# LED.net
KiCad netlist of a schematic drawn in Altium Designer
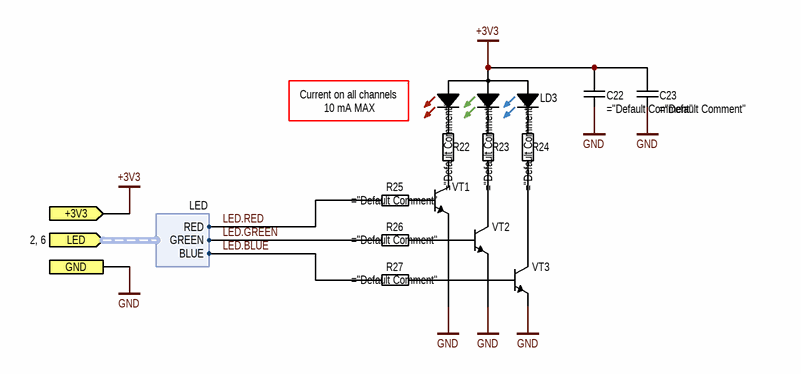
[diagram p0: LED.SchDoc]

(export (version "E")
  (design (tool "Eeschema 10.0.6"))
  (components
    (comp (ref "C22")
      (value "~")
      (description "CAP CER 10UF 10V X5R 0805")
      (fields (field (name "TOLERANCE") "10 %") (field (name "MANUFACTURER") "YAGEO"))
      (libsource (lib "femtoino") (part "CC0805KPX5R6BB106"))
    )
    (comp (ref "C23")
      (value "~")
      (description "CAP CER 1UF 10V X5R 0805")
      (fields (field (name "TOLERANCE") "10 %") (field (name "MANUFACTURER") "YAGEO"))
      (libsource (lib "femtoino") (part "CC0805KKX5R6BB105"))
    )
    (comp (ref "LD3")
      (value "~")
      (description "LED RGB DIFFUSED SMD")
      (fields (field (name "TOLERANCE") "* %") (field (name "MANUFACTURER") "Würth Elektronik"))
      (libsource (lib "femtoino") (part "150066M153000"))
    )
    (comp (ref "R22")
      (value "~")
      (description "RES 10 OHM 1% 1/10W 0603")
      (fields (field (name "TOLERANCE") "1 %") (field (name "MANUFACTURER") "YAGEO"))
      (libsource (lib "femtoino") (part "RC0603FR-0710RL"))
    )
    (comp (ref "R23")
      (value "~")
      (description "RES 10 OHM 1% 1/10W 0603")
      (fields (field (name "TOLERANCE") "1 %") (field (name "MANUFACTURER") "YAGEO"))
      (libsource (lib "femtoino") (part "RC0603FR-0710RL"))
    )
    (comp (ref "R24")
      (value "~")
      (description "RES 133 OHM 1% 1/10W 0603")
      (fields (field (name "TOLERANCE") "1 %") (field (name "MANUFACTURER") "YAGEO"))
      (libsource (lib "femtoino") (part "RC0603FR-07133RL"))
    )
    (comp (ref "R25")
      (value "~")
      (description "RES 1K OHM 1% 1/10W 0603")
      (fields (field (name "TOLERANCE") "1 %") (field (name "MANUFACTURER") "YAGEO"))
      (libsource (lib "femtoino") (part "RC0603FR-071KL"))
    )
    (comp (ref "R26")
      (value "~")
      (description "RES 1K OHM 1% 1/10W 0603")
      (fields (field (name "TOLERANCE") "1 %") (field (name "MANUFACTURER") "YAGEO"))
      (libsource (lib "femtoino") (part "RC0603FR-071KL"))
    )
    (comp (ref "R27")
      (value "~")
      (description "RES 1K OHM 1% 1/10W 0603")
      (fields (field (name "TOLERANCE") "1 %") (field (name "MANUFACTURER") "YAGEO"))
      (libsource (lib "femtoino") (part "RC0603FR-071KL"))
    )
    (comp (ref "VT1")
      (value "~")
      (description "TRANS NPN 40V 0.6A SOT23")
      (fields (field (name "TOLERANCE") "* %") (field (name "MANUFACTURER") "Micro Commercial Co"))
      (libsource (lib "femtoino") (part "MMBT2222A-TP"))
    )
    (comp (ref "VT2")
      (value "~")
      (description "TRANS NPN 40V 0.6A SOT23")
      (fields (field (name "TOLERANCE") "* %") (field (name "MANUFACTURER") "Micro Commercial Co"))
      (libsource (lib "femtoino") (part "MMBT2222A-TP"))
    )
    (comp (ref "VT3")
      (value "~")
      (description "TRANS NPN 40V 0.6A SOT23")
      (fields (field (name "TOLERANCE") "* %") (field (name "MANUFACTURER") "Micro Commercial Co"))
      (libsource (lib "femtoino") (part "MMBT2222A-TP"))
    )
  )
  (nets
    (net (code "2") (name "+3V3") (class "Default")
      (node (ref "C22") (pin "2") (pinfunction "2_2") (pintype "passive"))
      (node (ref "C23") (pin "2") (pinfunction "2_2") (pintype "passive"))
      (node (ref "LD3") (pin "CA") (pinfunction "CA_CA") (pintype "passive"))
    )
    (net (code "3") (name "/LED.BLUE") (class "Default")
      (node (ref "R27") (pin "1") (pinfunction "1_1") (pintype "passive"))
    )
    (net (code "4") (name "/LED.GREEN") (class "Default")
      (node (ref "R26") (pin "1") (pinfunction "1_1") (pintype "passive"))
    )
    (net (code "5") (name "/LED.RED") (class "Default")
      (node (ref "R25") (pin "1") (pinfunction "1_1") (pintype "passive"))
    )
    (net (code "7") (name "GND") (class "Default")
      (node (ref "C22") (pin "1") (pinfunction "1_1") (pintype "passive"))
      (node (ref "C23") (pin "1") (pinfunction "1_1") (pintype "passive"))
      (node (ref "VT1") (pin "E") (pinfunction "E_E") (pintype "passive"))
      (node (ref "VT2") (pin "E") (pinfunction "E_E") (pintype "passive"))
      (node (ref "VT3") (pin "E") (pinfunction "E_E") (pintype "passive"))
    )
    (net (code "8") (name "Net-(LD3-PadBC)") (class "Default")
      (node (ref "LD3") (pin "BC") (pinfunction "BC_BC") (pintype "passive"))
      (node (ref "R24") (pin "2") (pinfunction "2_2") (pintype "passive"))
    )
    (net (code "9") (name "Net-(LD3-PadGC)") (class "Default")
      (node (ref "LD3") (pin "GC") (pinfunction "GC_GC") (pintype "passive"))
      (node (ref "R23") (pin "2") (pinfunction "2_2") (pintype "passive"))
    )
    (net (code "10") (name "Net-(LD3-PadRC)") (class "Default")
      (node (ref "LD3") (pin "RC") (pinfunction "RC_RC") (pintype "passive"))
      (node (ref "R22") (pin "2") (pinfunction "2_2") (pintype "passive"))
    )
    (net (code "11") (name "Net-(R22-Pad1)") (class "Default")
      (node (ref "R22") (pin "1") (pinfunction "1_1") (pintype "passive"))
      (node (ref "VT1") (pin "C") (pinfunction "C_C") (pintype "passive"))
    )
    (net (code "12") (name "Net-(R23-Pad1)") (class "Default")
      (node (ref "R23") (pin "1") (pinfunction "1_1") (pintype "passive"))
      (node (ref "VT2") (pin "C") (pinfunction "C_C") (pintype "passive"))
    )
    (net (code "13") (name "Net-(R24-Pad1)") (class "Default")
      (node (ref "R24") (pin "1") (pinfunction "1_1") (pintype "passive"))
      (node (ref "VT3") (pin "C") (pinfunction "C_C") (pintype "passive"))
    )
    (net (code "14") (name "Net-(R25-Pad2)") (class "Default")
      (node (ref "R25") (pin "2") (pinfunction "2_2") (pintype "passive"))
      (node (ref "VT1") (pin "B") (pinfunction "B_B") (pintype "passive"))
    )
    (net (code "15") (name "Net-(R26-Pad2)") (class "Default")
      (node (ref "R26") (pin "2") (pinfunction "2_2") (pintype "passive"))
      (node (ref "VT2") (pin "B") (pinfunction "B_B") (pintype "passive"))
    )
    (net (code "16") (name "Net-(R27-Pad2)") (class "Default")
      (node (ref "R27") (pin "2") (pinfunction "2_2") (pintype "passive"))
      (node (ref "VT3") (pin "B") (pinfunction "B_B") (pintype "passive"))
    )
  )
)
